# TPT02rrr.net
KiCad netlist of a schematic drawn in EAGLE
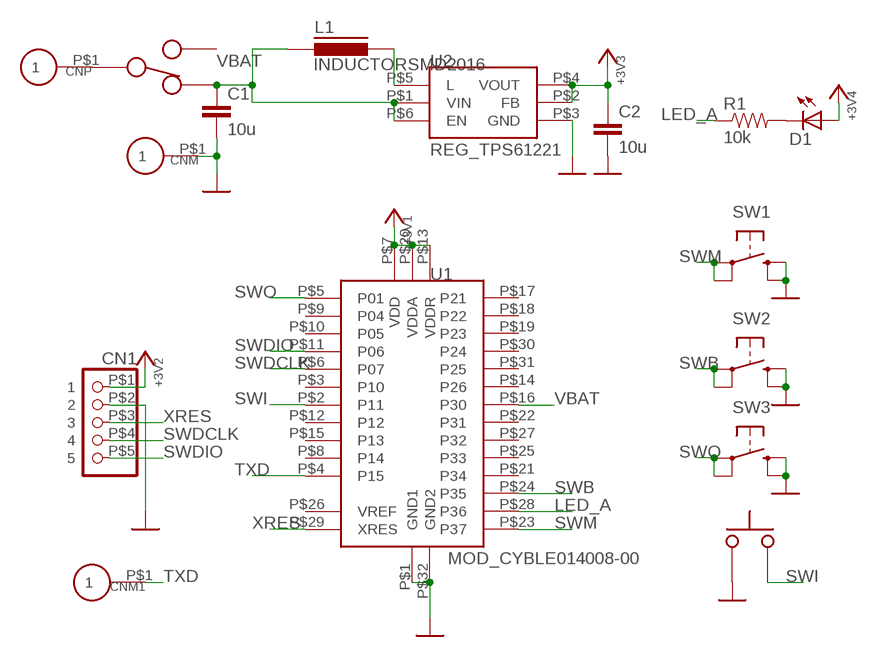
[diagram p0: schematic, sheet 1]

(export (version "E")
  (design (tool "Eeschema 10.0.6"))
  (components
    (comp (ref "C1")
      (value "10u")
      (footprint "eagle-import:0603")
      (libsource (lib "eagle-import") (part "CAP0603"))
    )
    (comp (ref "C2")
      (value "10u")
      (footprint "eagle-import:0603")
      (libsource (lib "eagle-import") (part "CAP0603"))
    )
    (comp (ref "CN1")
      (value "CON_PINHD-1X550MIL")
      (footprint "eagle-import:1X5_50MIL")
      (libsource (lib "eagle-import") (part "CON_PINHD-1X550MIL"))
    )
    (comp (ref "CNM")
      (value "CON_P01SMD1MM")
      (footprint "eagle-import:PAD_SMD1MM")
      (libsource (lib "eagle-import") (part "CON_P01SMD1MM"))
    )
    (comp (ref "CNM1")
      (value "CON_P01SMD1MM")
      (footprint "eagle-import:PAD_SMD1MM")
      (libsource (lib "eagle-import") (part "CON_P01SMD1MM"))
    )
    (comp (ref "CNP")
      (value "CON_P01SMD1MM")
      (footprint "eagle-import:PAD_SMD1MM")
      (libsource (lib "eagle-import") (part "CON_P01SMD1MM"))
    )
    (comp (ref "D1")
      (value "LED0603")
      (footprint "eagle-import:SPARKFUN_LED-0603")
      (libsource (lib "eagle-import") (part "LED0603"))
    )
    (comp (ref "L1")
      (value "INDUCTORSMD2016")
      (footprint "eagle-import:2016")
      (libsource (lib "eagle-import") (part "INDUCTORSMD2016"))
    )
    (comp (ref "R1")
      (value "10k")
      (footprint "eagle-import:0603")
      (libsource (lib "eagle-import") (part "RES0603"))
    )
    (comp (ref "SW1")
      (value "SW_TACTEVQP2")
      (footprint "eagle-import:SW_EVQP2")
      (libsource (lib "eagle-import") (part "SW_TACTEVQP2"))
    )
    (comp (ref "SW2")
      (value "SW_TACTEVQPLBA08")
      (footprint "eagle-import:SW_EVQPLBA08")
      (libsource (lib "eagle-import") (part "SW_TACTEVQPLBA08"))
    )
    (comp (ref "SW3")
      (value "SW_TACTEVQPLBA08")
      (footprint "eagle-import:SW_EVQPLBA08")
      (libsource (lib "eagle-import") (part "SW_TACTEVQPLBA08"))
    )
    (comp (ref "SW4")
      (value "SW_SLIDECUS12B")
      (footprint "eagle-import:SW_CUS-12B")
      (libsource (lib "eagle-import") (part "SW_SLIDECUS12B"))
    )
    (comp (ref "SW5")
      (value "SW_TACT2PB3U3000")
      (footprint "eagle-import:SW_B3U-3000P")
      (libsource (lib "eagle-import") (part "SW_TACT2PB3U3000"))
    )
    (comp (ref "U1")
      (value "MOD_CYBLE014008-00")
      (footprint "eagle-import:MOD_CYBLE014008-00")
      (libsource (lib "eagle-import") (part "MOD_CYBLE014008-00"))
    )
    (comp (ref "U2")
      (value "REG_TPS61221")
      (footprint "eagle-import:SC70-6")
      (libsource (lib "eagle-import") (part "REG_TPS61221"))
    )
  )
  (nets
    (net (code "1") (name "/LED_A") (class "Default")
      (node (ref "R1") (pin "1") (pinfunction "1_1") (pintype "passive"))
      (node (ref "U1") (pin "P$28") (pinfunction "P36_P$28") (pintype "bidirectional"))
    )
    (net (code "2") (name "/P$3") (class "Default")
      (node (ref "SW4") (pin "P$3") (pinfunction "P$3_P$3") (pintype "power_in"))
    )
    (net (code "3") (name "/SWB") (class "Default")
      (node (ref "SW2") (pin "A1") (pinfunction "P_A1") (pintype "passive"))
      (node (ref "SW2") (pin "A2") (pinfunction "P1_A2") (pintype "passive"))
      (node (ref "U1") (pin "P$24") (pinfunction "P35_P$24") (pintype "bidirectional"))
    )
    (net (code "4") (name "/SWDCLK") (class "Default")
      (node (ref "CN1") (pin "P$4") (pinfunction "4_P$4") (pintype "passive"))
      (node (ref "U1") (pin "P$6") (pinfunction "P07_P$6") (pintype "bidirectional"))
    )
    (net (code "5") (name "/SWDIO") (class "Default")
      (node (ref "CN1") (pin "P$5") (pinfunction "5_P$5") (pintype "passive"))
      (node (ref "U1") (pin "P$11") (pinfunction "P06_P$11") (pintype "bidirectional"))
    )
    (net (code "6") (name "/SWI") (class "Default")
      (node (ref "SW5") (pin "P$1") (pinfunction "P$1_P$1") (pintype "passive"))
      (node (ref "U1") (pin "P$2") (pinfunction "P11_P$2") (pintype "bidirectional"))
    )
    (net (code "7") (name "/SWM") (class "Default")
      (node (ref "SW1") (pin "PA1") (pinfunction "P_PA1") (pintype "passive"))
      (node (ref "SW1") (pin "PA2") (pinfunction "P1_PA2") (pintype "passive"))
      (node (ref "U1") (pin "P$23") (pinfunction "P37_P$23") (pintype "bidirectional"))
    )
    (net (code "8") (name "/SWO") (class "Default")
      (node (ref "SW3") (pin "A1") (pinfunction "P_A1") (pintype "passive"))
      (node (ref "SW3") (pin "A2") (pinfunction "P1_A2") (pintype "passive"))
      (node (ref "U1") (pin "P$5") (pinfunction "P01_P$5") (pintype "bidirectional"))
    )
    (net (code "9") (name "/TXD") (class "Default")
      (node (ref "CNM1") (pin "P$1") (pinfunction "1_P$1") (pintype "bidirectional"))
      (node (ref "U1") (pin "P$4") (pinfunction "P15_P$4") (pintype "bidirectional"))
    )
    (net (code "10") (name "/VBAT") (class "Default")
      (node (ref "C1") (pin "1") (pinfunction "1_1") (pintype "passive"))
      (node (ref "L1") (pin "P$1") (pinfunction "1_P$1") (pintype "passive"))
      (node (ref "SW4") (pin "P$1") (pinfunction "P$1_P$1") (pintype "power_in"))
      (node (ref "U1") (pin "P$16") (pinfunction "P30_P$16") (pintype "bidirectional"))
      (node (ref "U2") (pin "P$1") (pinfunction "VIN_P$1") (pintype "bidirectional"))
      (node (ref "U2") (pin "P$6") (pinfunction "EN_P$6") (pintype "bidirectional"))
    )
    (net (code "11") (name "/XRES") (class "Default")
      (node (ref "CN1") (pin "P$3") (pinfunction "3_P$3") (pintype "passive"))
      (node (ref "U1") (pin "P$29") (pinfunction "XRES_P$29") (pintype "bidirectional"))
    )
    (net (code "12") (name "Net-(CNP-1)") (class "Default")
      (node (ref "CNP") (pin "P$1") (pinfunction "1_P$1") (pintype "bidirectional"))
      (node (ref "SW4") (pin "P$2") (pinfunction "P$2_P$2") (pintype "power_in"))
    )
    (net (code "13") (name "Net-(D1-PadC)") (class "Default")
      (node (ref "D1") (pin "C") (pinfunction "C_C") (pintype "passive"))
      (node (ref "R1") (pin "2") (pinfunction "2_2") (pintype "passive"))
    )
    (net (code "14") (name "Net-(L1-2)") (class "Default")
      (node (ref "L1") (pin "P$2") (pinfunction "2_P$2") (pintype "passive"))
      (node (ref "U2") (pin "P$5") (pinfunction "L_P$5") (pintype "bidirectional"))
    )
    (net (code "15") (name "POW_+3V3") (class "Default")
      (node (ref "C2") (pin "1") (pinfunction "1_1") (pintype "passive"))
      (node (ref "CN1") (pin "P$1") (pinfunction "1_P$1") (pintype "passive"))
      (node (ref "D1") (pin "A") (pinfunction "A_A") (pintype "passive"))
      (node (ref "U1") (pin "P$13") (pinfunction "VDDR_P$13") (pintype "bidirectional"))
      (node (ref "U1") (pin "P$20") (pinfunction "VDDA_P$20") (pintype "bidirectional"))
      (node (ref "U1") (pin "P$7") (pinfunction "VDD_P$7") (pintype "bidirectional"))
      (node (ref "U2") (pin "P$2") (pinfunction "FB_P$2") (pintype "bidirectional"))
      (node (ref "U2") (pin "P$4") (pinfunction "VOUT_P$4") (pintype "bidirectional"))
    )
    (net (code "16") (name "POW_GND") (class "Default")
      (node (ref "C1") (pin "2") (pinfunction "2_2") (pintype "passive"))
      (node (ref "C2") (pin "2") (pinfunction "2_2") (pintype "passive"))
      (node (ref "CN1") (pin "P$2") (pinfunction "2_P$2") (pintype "passive"))
      (node (ref "CNM") (pin "P$1") (pinfunction "1_P$1") (pintype "bidirectional"))
      (node (ref "SW1") (pin "PB1") (pinfunction "S_PB1") (pintype "passive"))
      (node (ref "SW1") (pin "PB2") (pinfunction "S1_PB2") (pintype "passive"))
      (node (ref "SW2") (pin "B1") (pinfunction "S_B1") (pintype "passive"))
      (node (ref "SW2") (pin "B2") (pinfunction "S1_B2") (pintype "passive"))
      (node (ref "SW3") (pin "B1") (pinfunction "S_B1") (pintype "passive"))
      (node (ref "SW3") (pin "B2") (pinfunction "S1_B2") (pintype "passive"))
      (node (ref "SW5") (pin "P$2") (pinfunction "P$2_P$2") (pintype "passive"))
      (node (ref "U1") (pin "P$1") (pinfunction "GND1_P$1") (pintype "bidirectional"))
      (node (ref "U1") (pin "P$32") (pinfunction "GND2_P$32") (pintype "bidirectional"))
      (node (ref "U2") (pin "P$3") (pinfunction "GND_P$3") (pintype "bidirectional"))
    )
    (net (code "17") (name "unconnected-(U1-P04-PadP$9)") (class "Default")
      (node (ref "U1") (pin "P$9") (pinfunction "P04_P$9") (pintype "bidirectional"))
    )
    (net (code "18") (name "unconnected-(U1-P05-PadP$10)") (class "Default")
      (node (ref "U1") (pin "P$10") (pinfunction "P05_P$10") (pintype "bidirectional"))
    )
    (net (code "19") (name "unconnected-(U1-P10-PadP$3)") (class "Default")
      (node (ref "U1") (pin "P$3") (pinfunction "P10_P$3") (pintype "bidirectional"))
    )
    (net (code "20") (name "unconnected-(U1-P12-PadP$12)") (class "Default")
      (node (ref "U1") (pin "P$12") (pinfunction "P12_P$12") (pintype "bidirectional"))
    )
    (net (code "21") (name "unconnected-(U1-P13-PadP$15)") (class "Default")
      (node (ref "U1") (pin "P$15") (pinfunction "P13_P$15") (pintype "bidirectional"))
    )
    (net (code "22") (name "unconnected-(U1-P14-PadP$8)") (class "Default")
      (node (ref "U1") (pin "P$8") (pinfunction "P14_P$8") (pintype "bidirectional"))
    )
    (net (code "23") (name "unconnected-(U1-P21-PadP$17)") (class "Default")
      (node (ref "U1") (pin "P$17") (pinfunction "P21_P$17") (pintype "bidirectional"))
    )
    (net (code "24") (name "unconnected-(U1-P22-PadP$18)") (class "Default")
      (node (ref "U1") (pin "P$18") (pinfunction "P22_P$18") (pintype "bidirectional"))
    )
    (net (code "25") (name "unconnected-(U1-P23-PadP$19)") (class "Default")
      (node (ref "U1") (pin "P$19") (pinfunction "P23_P$19") (pintype "bidirectional"))
    )
    (net (code "26") (name "unconnected-(U1-P24-PadP$30)") (class "Default")
      (node (ref "U1") (pin "P$30") (pinfunction "P24_P$30") (pintype "bidirectional"))
    )
    (net (code "27") (name "unconnected-(U1-P25-PadP$31)") (class "Default")
      (node (ref "U1") (pin "P$31") (pinfunction "P25_P$31") (pintype "bidirectional"))
    )
    (net (code "28") (name "unconnected-(U1-P26-PadP$14)") (class "Default")
      (node (ref "U1") (pin "P$14") (pinfunction "P26_P$14") (pintype "bidirectional"))
    )
    (net (code "29") (name "unconnected-(U1-P31-PadP$22)") (class "Default")
      (node (ref "U1") (pin "P$22") (pinfunction "P31_P$22") (pintype "bidirectional"))
    )
    (net (code "30") (name "unconnected-(U1-P32-PadP$27)") (class "Default")
      (node (ref "U1") (pin "P$27") (pinfunction "P32_P$27") (pintype "bidirectional"))
    )
    (net (code "31") (name "unconnected-(U1-P33-PadP$25)") (class "Default")
      (node (ref "U1") (pin "P$25") (pinfunction "P33_P$25") (pintype "bidirectional"))
    )
    (net (code "32") (name "unconnected-(U1-P34-PadP$21)") (class "Default")
      (node (ref "U1") (pin "P$21") (pinfunction "P34_P$21") (pintype "bidirectional"))
    )
    (net (code "33") (name "unconnected-(U1-VREF-PadP$26)") (class "Default")
      (node (ref "U1") (pin "P$26") (pinfunction "VREF_P$26") (pintype "bidirectional"))
    )
  )
)
